# PowerSupply.net
KiCad netlist of a schematic drawn in Altium Designer
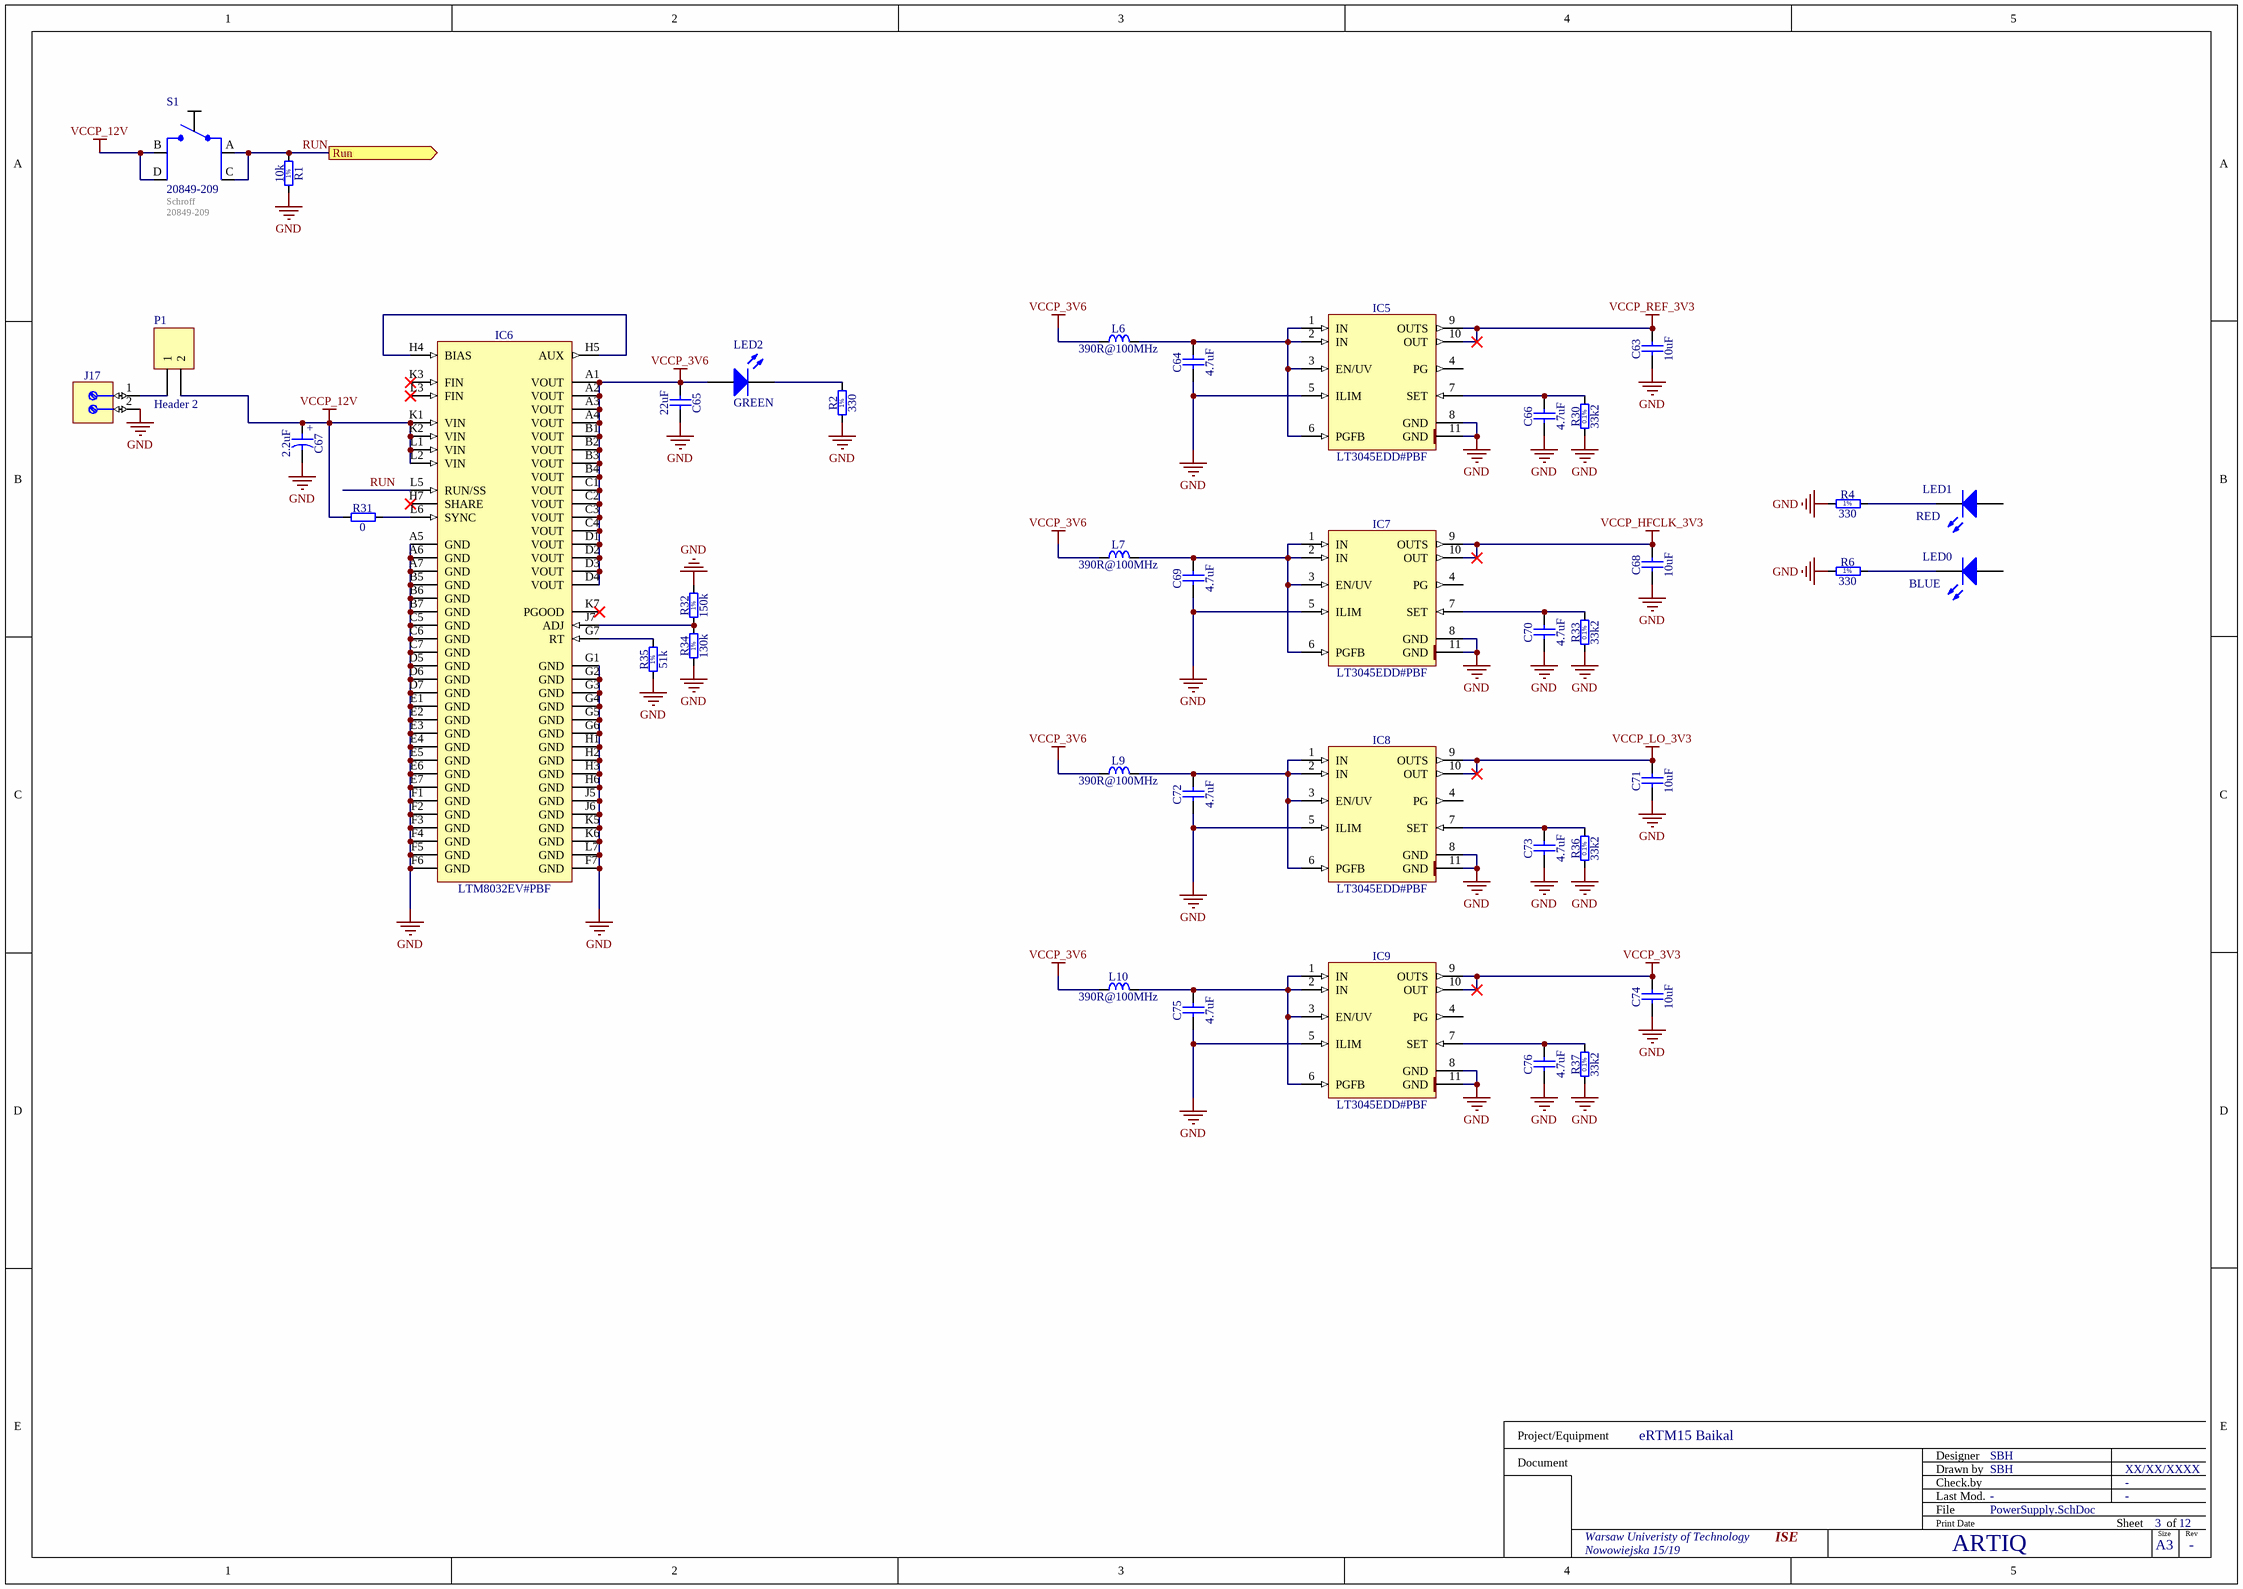
[diagram p0: PowerSupply.SchDoc]

(export (version "E")
  (design (tool "Eeschema 10.0.6"))
  (components
    (comp (ref "C63")
      (value "10uF")
      (footprint "CAPC1608X87N")
      (description "Non-polarised capacitor")
      (fields
        (field (name "PART NUMBER") "CC0603_10UF_6.3V_20%_X5R")
        (field (name "VOLTAGE") "6.3V")
        (field (name "AUTHOR") "CERN DEM JLC")
      )
      (libsource (lib "Capacitors") (part "Capacitor - non polarized"))
    )
    (comp (ref "C64")
      (value "4.7uF")
      (footprint "CAPC1709X95N")
      (description "Non-polarised capacitor")
      (fields
        (field (name "PART NUMBER") "CC0603_4.7UF_16V_10%_X5R")
        (field (name "VOLTAGE") "16V")
        (field (name "AUTHOR") "CERN DEM JLC")
      )
      (libsource (lib "Capacitors") (part "Capacitor - non polarized"))
    )
    (comp (ref "C65")
      (value "22uF")
      (footprint "CAPC3216X180N")
      (description "Non-polarised capacitor")
      (fields
        (field (name "PART NUMBER") "CC1206_22UF_10V_10%_X7R")
        (field (name "VOLTAGE") "10V")
        (field (name "AUTHOR") "CERN DEM JLC")
      )
      (libsource (lib "Capacitors") (part "Capacitor - non polarized"))
    )
    (comp (ref "C66")
      (value "4.7uF")
      (footprint "CAPC1709X95N")
      (description "Non-polarised capacitor")
      (fields
        (field (name "PART NUMBER") "CC0603_4.7UF_16V_10%_X5R")
        (field (name "VOLTAGE") "16V")
        (field (name "AUTHOR") "CERN DEM JLC")
      )
      (libsource (lib "Capacitors") (part "Capacitor - non polarized"))
    )
    (comp (ref "C67")
      (value "2.2uF")
      (footprint "CAPMP3216X180N")
      (description "Polarised capacitor")
      (fields
        (field (name "PART NUMBER") "CTE3216-18_2.2UF_25V_10%")
        (field (name "VOLTAGE") "25V")
        (field (name "AUTHOR") "CERN DEM JLC")
      )
      (libsource (lib "Capacitors") (part "Capacitor - polarized"))
    )
    (comp (ref "C68")
      (value "10uF")
      (footprint "CAPC1608X87N")
      (description "Non-polarised capacitor")
      (fields
        (field (name "PART NUMBER") "CC0603_10UF_6.3V_20%_X5R")
        (field (name "VOLTAGE") "6.3V")
        (field (name "AUTHOR") "CERN DEM JLC")
      )
      (libsource (lib "Capacitors") (part "Capacitor - non polarized"))
    )
    (comp (ref "C69")
      (value "4.7uF")
      (footprint "CAPC1709X95N")
      (description "Non-polarised capacitor")
      (fields
        (field (name "PART NUMBER") "CC0603_4.7UF_16V_10%_X5R")
        (field (name "VOLTAGE") "16V")
        (field (name "AUTHOR") "CERN DEM JLC")
      )
      (libsource (lib "Capacitors") (part "Capacitor - non polarized"))
    )
    (comp (ref "C70")
      (value "4.7uF")
      (footprint "CAPC1709X95N")
      (description "Non-polarised capacitor")
      (fields
        (field (name "PART NUMBER") "CC0603_4.7UF_16V_10%_X5R")
        (field (name "VOLTAGE") "16V")
        (field (name "AUTHOR") "CERN DEM JLC")
      )
      (libsource (lib "Capacitors") (part "Capacitor - non polarized"))
    )
    (comp (ref "C71")
      (value "10uF")
      (footprint "CAPC1608X87N")
      (description "Non-polarised capacitor")
      (fields
        (field (name "PART NUMBER") "CC0603_10UF_6.3V_20%_X5R")
        (field (name "VOLTAGE") "6.3V")
        (field (name "AUTHOR") "CERN DEM JLC")
      )
      (libsource (lib "Capacitors") (part "Capacitor - non polarized"))
    )
    (comp (ref "C72")
      (value "4.7uF")
      (footprint "CAPC1709X95N")
      (description "Non-polarised capacitor")
      (fields
        (field (name "PART NUMBER") "CC0603_4.7UF_16V_10%_X5R")
        (field (name "VOLTAGE") "16V")
        (field (name "AUTHOR") "CERN DEM JLC")
      )
      (libsource (lib "Capacitors") (part "Capacitor - non polarized"))
    )
    (comp (ref "C73")
      (value "4.7uF")
      (footprint "CAPC1709X95N")
      (description "Non-polarised capacitor")
      (fields
        (field (name "PART NUMBER") "CC0603_4.7UF_16V_10%_X5R")
        (field (name "VOLTAGE") "16V")
        (field (name "AUTHOR") "CERN DEM JLC")
      )
      (libsource (lib "Capacitors") (part "Capacitor - non polarized"))
    )
    (comp (ref "C74")
      (value "10uF")
      (footprint "CAPC1608X87N")
      (description "Non-polarised capacitor")
      (fields
        (field (name "PART NUMBER") "CC0603_10UF_6.3V_20%_X5R")
        (field (name "VOLTAGE") "6.3V")
        (field (name "AUTHOR") "CERN DEM JLC")
      )
      (libsource (lib "Capacitors") (part "Capacitor - non polarized"))
    )
    (comp (ref "C75")
      (value "4.7uF")
      (footprint "CAPC1709X95N")
      (description "Non-polarised capacitor")
      (fields
        (field (name "PART NUMBER") "CC0603_4.7UF_16V_10%_X5R")
        (field (name "VOLTAGE") "16V")
        (field (name "AUTHOR") "CERN DEM JLC")
      )
      (libsource (lib "Capacitors") (part "Capacitor - non polarized"))
    )
    (comp (ref "C76")
      (value "4.7uF")
      (footprint "CAPC1709X95N")
      (description "Non-polarised capacitor")
      (fields
        (field (name "PART NUMBER") "CC0603_4.7UF_16V_10%_X5R")
        (field (name "VOLTAGE") "16V")
        (field (name "AUTHOR") "CERN DEM JLC")
      )
      (libsource (lib "Capacitors") (part "Capacitor - non polarized"))
    )
    (comp (ref "IC5")
      (value "LT3045EDD#PBF")
      (footprint "SON50P300X300X80-11N-R175X248")
      (description "20V, 500mA, Ultralow Noise, Ultrahigh PSRR Linear Regulator")
      (fields (field (name "MANUFACTURER") "LINEAR TECHNOLOGY") (field (name "AUTHOR") "CERN DEM JLC"))
      (libsource (lib "ICs And Semiconductors") (part "LT3045EDD"))
    )
    (comp (ref "IC6")
      (value "LTM8032EV#PBF")
      (footprint "LGA71S127P7X11_900X1500X297")
      (description "3V-36V To 0.8V-10V, Iout 2A Ultralow Noise EMC Compliant DC/DC uModule")
      (fields (field (name "MANUFACTURER") "LINEAR TECHNOLOGY") (field (name "AUTHOR") "CERN DEM JLC"))
      (libsource (lib "ICs And Semiconductors") (part "LTM8032"))
    )
    (comp (ref "IC7")
      (value "LT3045EDD#PBF")
      (footprint "SON50P300X300X80-11N-R175X248")
      (description "20V, 500mA, Ultralow Noise, Ultrahigh PSRR Linear Regulator")
      (fields (field (name "MANUFACTURER") "LINEAR TECHNOLOGY") (field (name "AUTHOR") "CERN DEM JLC"))
      (libsource (lib "ICs And Semiconductors") (part "LT3045EDD"))
    )
    (comp (ref "IC8")
      (value "LT3045EDD#PBF")
      (footprint "SON50P300X300X80-11N-R175X248")
      (description "20V, 500mA, Ultralow Noise, Ultrahigh PSRR Linear Regulator")
      (fields (field (name "MANUFACTURER") "LINEAR TECHNOLOGY") (field (name "AUTHOR") "CERN DEM JLC"))
      (libsource (lib "ICs And Semiconductors") (part "LT3045EDD"))
    )
    (comp (ref "IC9")
      (value "LT3045EDD#PBF")
      (footprint "SON50P300X300X80-11N-R175X248")
      (description "20V, 500mA, Ultralow Noise, Ultrahigh PSRR Linear Regulator")
      (fields (field (name "MANUFACTURER") "LINEAR TECHNOLOGY") (field (name "AUTHOR") "CERN DEM JLC"))
      (libsource (lib "ICs And Semiconductors") (part "LT3045EDD"))
    )
    (comp (ref "J17")
      (value "Terminal")
      (footprint "WIELAND_25.161.0253.0")
      (description "Terminal Block, 2 Positions, Screw Connection")
      (fields
        (field (name "PART NUMBER") "WIELAND_25.161.0253.0")
        (field (name "MANUFACTURER") "WIELAND")
        (field (name "AUTHOR") "CERN DEM JLC")
      )
      (libsource (lib "Connectors") (part "Terminal Block_2 Positions_Screw Connection"))
    )
    (comp (ref "L6")
      (value "390R@100MHz")
      (footprint "INDC1608X95N")
      (description "Inductor")
      (fields
        (field (name "PART NUMBER") "IND0603_TDK_MPZ1608R391A")
        (field (name "POWER") "1.2A")
        (field (name "AUTHOR") "CERN DEM JLC")
      )
      (libsource (lib "Inductors & Transformers") (part "Inductor"))
    )
    (comp (ref "L7")
      (value "390R@100MHz")
      (footprint "INDC1608X95N")
      (description "Inductor")
      (fields
        (field (name "PART NUMBER") "IND0603_TDK_MPZ1608R391A")
        (field (name "POWER") "1.2A")
        (field (name "AUTHOR") "CERN DEM JLC")
      )
      (libsource (lib "Inductors & Transformers") (part "Inductor"))
    )
    (comp (ref "L9")
      (value "390R@100MHz")
      (footprint "INDC1608X95N")
      (description "Inductor")
      (fields
        (field (name "PART NUMBER") "IND0603_TDK_MPZ1608R391A")
        (field (name "POWER") "1.2A")
        (field (name "AUTHOR") "CERN DEM JLC")
      )
      (libsource (lib "Inductors & Transformers") (part "Inductor"))
    )
    (comp (ref "L10")
      (value "390R@100MHz")
      (footprint "INDC1608X95N")
      (description "Inductor")
      (fields
        (field (name "PART NUMBER") "IND0603_TDK_MPZ1608R391A")
        (field (name "POWER") "1.2A")
        (field (name "AUTHOR") "CERN DEM JLC")
      )
      (libsource (lib "Inductors & Transformers") (part "Inductor"))
    )
    (comp (ref "LED0")
      (value "BLUE")
      (footprint "0603LED")
      (description "LED")
      (libsource (lib "Miscellaneous Devices") (part "LED2"))
    )
    (comp (ref "LED1")
      (value "RED")
      (footprint "0603LED")
      (description "LED")
      (libsource (lib "Miscellaneous Devices") (part "LED3"))
    )
    (comp (ref "LED2")
      (value "GREEN")
      (footprint "0603LED")
      (description "LED")
      (libsource (lib "Miscellaneous Devices") (part "LED3"))
    )
    (comp (ref "P1")
      (value "Header 2")
      (footprint "HDR1X2")
      (description "Header, 2-Pin")
      (fields (field (name "PUBLISHER") "Altium Limited"))
      (libsource (lib "Miscellaneous Connectors") (part "Header 2"))
    )
    (comp (ref "R1")
      (value "10k")
      (footprint "RESC1005X40N")
      (description "Resistor - 1%")
      (fields
        (field (name "PART NUMBER") "R0402_10K_1%_0.0625W_100PPM")
        (field (name "POWER") "0.0625W")
        (field (name "AUTHOR") "CERN DEM JLC")
      )
      (libsource (lib "Resistors") (part "Resistor - 1%"))
    )
    (comp (ref "R2")
      (value "330")
      (footprint "RESC1005X40N")
      (description "Resistor - 1%")
      (fields
        (field (name "PART NUMBER") "R0402_330R_1%_0.0625W_100PPM")
        (field (name "POWER") "0.0625W")
        (field (name "AUTHOR") "CERN DEM JLC")
      )
      (libsource (lib "Resistors") (part "Resistor - 1%"))
    )
    (comp (ref "R4")
      (value "330")
      (footprint "RESC1005X40N")
      (description "Resistor - 1%")
      (fields
        (field (name "PART NUMBER") "R0402_330R_1%_0.0625W_100PPM")
        (field (name "POWER") "0.0625W")
        (field (name "AUTHOR") "CERN DEM JLC")
      )
      (libsource (lib "Resistors") (part "Resistor - 1%"))
    )
    (comp (ref "R6")
      (value "330")
      (footprint "RESC1005X40N")
      (description "Resistor - 1%")
      (fields
        (field (name "PART NUMBER") "R0402_330R_1%_0.0625W_100PPM")
        (field (name "POWER") "0.0625W")
        (field (name "AUTHOR") "CERN DEM JLC")
      )
      (libsource (lib "Resistors") (part "Resistor - 1%"))
    )
    (comp (ref "R30")
      (value "33k2")
      (footprint "RESC1608X55N")
      (description "Resistor - 0.1%")
      (fields
        (field (name "PART NUMBER") "R0603_33K2_0.1%_0.063W_10PPM")
        (field (name "POWER") "0.063W")
        (field (name "AUTHOR") "CERN DEM JLC")
      )
      (libsource (lib "Resistors") (part "Resistor - 0.1%"))
    )
    (comp (ref "R31")
      (value "0")
      (footprint "RESC1005X40N")
      (description "Resistor")
      (fields
        (field (name "PART NUMBER") "R0402_0R_JUMPER")
        (field (name "MANUFACTURER") "GENERIC")
        (field (name "AUTHOR") "CERN DEM JLC")
      )
      (libsource (lib "Resistors") (part "Resistor"))
    )
    (comp (ref "R32")
      (value "150k")
      (footprint "RESC1005X40N")
      (description "Resistor - 1%")
      (fields
        (field (name "PART NUMBER") "R0402_150K_1%_0.0625W_100PPM")
        (field (name "POWER") "0.0625W")
        (field (name "AUTHOR") "CERN DEM JLC")
      )
      (libsource (lib "Resistors") (part "Resistor - 1%"))
    )
    (comp (ref "R33")
      (value "33k2")
      (footprint "RESC1608X55N")
      (description "Resistor - 0.1%")
      (fields
        (field (name "PART NUMBER") "R0603_33K2_0.1%_0.063W_10PPM")
        (field (name "POWER") "0.063W")
        (field (name "AUTHOR") "CERN DEM JLC")
      )
      (libsource (lib "Resistors") (part "Resistor - 0.1%"))
    )
    (comp (ref "R34")
      (value "130k")
      (footprint "RESC1005X40N")
      (description "Resistor - 1%")
      (fields
        (field (name "PART NUMBER") "R0402_130K_1%_0.0625W_100PPM")
        (field (name "POWER") "0.0625W")
        (field (name "AUTHOR") "CERN DEM JLC")
      )
      (libsource (lib "Resistors") (part "Resistor - 1%"))
    )
    (comp (ref "R35")
      (value "51k")
      (footprint "RESC1005X40N")
      (description "Resistor - 1%")
      (fields
        (field (name "PART NUMBER") "R0402_51K_1%_0.0625W_100PPM")
        (field (name "POWER") "0.0625W")
        (field (name "AUTHOR") "CERN DEM JLC")
      )
      (libsource (lib "Resistors") (part "Resistor - 1%"))
    )
    (comp (ref "R36")
      (value "33k2")
      (footprint "RESC1608X55N")
      (description "Resistor - 0.1%")
      (fields
        (field (name "PART NUMBER") "R0603_33K2_0.1%_0.063W_10PPM")
        (field (name "POWER") "0.063W")
        (field (name "AUTHOR") "CERN DEM JLC")
      )
      (libsource (lib "Resistors") (part "Resistor - 0.1%"))
    )
    (comp (ref "R37")
      (value "33k2")
      (footprint "RESC1608X55N")
      (description "Resistor - 0.1%")
      (fields
        (field (name "PART NUMBER") "R0603_33K2_0.1%_0.063W_10PPM")
        (field (name "POWER") "0.063W")
        (field (name "AUTHOR") "CERN DEM JLC")
      )
      (libsource (lib "Resistors") (part "Resistor - 0.1%"))
    )
    (comp (ref "S1")
      (value "20849-209")
      (footprint "4-pin Switch")
      (description "Mikroschalter fuer AMC-Modul (Schliesser)")
      (fields
        (field (name "MANUFACTURER") "Schroff")
        (field (name "DISTRIBUTOR") "Schroff")
        (field (name "DISTRIBUTORNR") "20849-209")
      )
      (libsource (lib "SchematicComponents") (part "4-pin Switch"))
    )
  )
  (nets
    (net (code "1") (name "/RUN") (class "Default")
      (node (ref "IC6") (pin "L5") (pinfunction "RUN/SS_L5") (pintype "input"))
      (node (ref "R1") (pin "2") (pinfunction "2_2") (pintype "passive"))
      (node (ref "S1") (pin "A") (pinfunction "A_A") (pintype "passive"))
      (node (ref "S1") (pin "C") (pinfunction "C_C") (pintype "passive"))
    )
    (net (code "2") (name "GND") (class "Default")
      (node (ref "C63") (pin "1") (pinfunction "1_1") (pintype "passive"))
      (node (ref "C64") (pin "1") (pinfunction "1_1") (pintype "passive"))
      (node (ref "C65") (pin "2") (pinfunction "2_2") (pintype "passive"))
      (node (ref "C66") (pin "1") (pinfunction "1_1") (pintype "passive"))
      (node (ref "C67") (pin "2") (pinfunction "2_2") (pintype "passive"))
      (node (ref "C68") (pin "1") (pinfunction "1_1") (pintype "passive"))
      (node (ref "C69") (pin "1") (pinfunction "1_1") (pintype "passive"))
      (node (ref "C70") (pin "1") (pinfunction "1_1") (pintype "passive"))
      (node (ref "C71") (pin "1") (pinfunction "1_1") (pintype "passive"))
      (node (ref "C72") (pin "1") (pinfunction "1_1") (pintype "passive"))
      (node (ref "C73") (pin "1") (pinfunction "1_1") (pintype "passive"))
      (node (ref "C74") (pin "1") (pinfunction "1_1") (pintype "passive"))
      (node (ref "C75") (pin "1") (pinfunction "1_1") (pintype "passive"))
      (node (ref "C76") (pin "1") (pinfunction "1_1") (pintype "passive"))
      (node (ref "IC5") (pin "11") (pinfunction "GND_11") (pintype "power_in"))
      (node (ref "IC5") (pin "5") (pinfunction "ILIM_5") (pintype "input"))
      (node (ref "IC5") (pin "8") (pinfunction "GND_8") (pintype "power_in"))
      (node (ref "IC6") (pin "A5") (pinfunction "GND_A5") (pintype "power_in"))
      (node (ref "IC6") (pin "A6") (pinfunction "GND_A6") (pintype "power_in"))
      (node (ref "IC6") (pin "A7") (pinfunction "GND_A7") (pintype "power_in"))
      (node (ref "IC6") (pin "B5") (pinfunction "GND_B5") (pintype "power_in"))
      (node (ref "IC6") (pin "B6") (pinfunction "GND_B6") (pintype "power_in"))
      (node (ref "IC6") (pin "B7") (pinfunction "GND_B7") (pintype "power_in"))
      (node (ref "IC6") (pin "C5") (pinfunction "GND_C5") (pintype "power_in"))
      (node (ref "IC6") (pin "C6") (pinfunction "GND_C6") (pintype "power_in"))
      (node (ref "IC6") (pin "C7") (pinfunction "GND_C7") (pintype "power_in"))
      (node (ref "IC6") (pin "D5") (pinfunction "GND_D5") (pintype "power_in"))
      (node (ref "IC6") (pin "D6") (pinfunction "GND_D6") (pintype "power_in"))
      (node (ref "IC6") (pin "D7") (pinfunction "GND_D7") (pintype "power_in"))
      (node (ref "IC6") (pin "E1") (pinfunction "GND_E1") (pintype "power_in"))
      (node (ref "IC6") (pin "E2") (pinfunction "GND_E2") (pintype "power_in"))
      (node (ref "IC6") (pin "E3") (pinfunction "GND_E3") (pintype "power_in"))
      (node (ref "IC6") (pin "E4") (pinfunction "GND_E4") (pintype "power_in"))
      (node (ref "IC6") (pin "E5") (pinfunction "GND_E5") (pintype "power_in"))
      (node (ref "IC6") (pin "E6") (pinfunction "GND_E6") (pintype "power_in"))
      (node (ref "IC6") (pin "E7") (pinfunction "GND_E7") (pintype "power_in"))
      (node (ref "IC6") (pin "F1") (pinfunction "GND_F1") (pintype "power_in"))
      (node (ref "IC6") (pin "F2") (pinfunction "GND_F2") (pintype "power_in"))
      (node (ref "IC6") (pin "F3") (pinfunction "GND_F3") (pintype "power_in"))
      (node (ref "IC6") (pin "F4") (pinfunction "GND_F4") (pintype "power_in"))
      (node (ref "IC6") (pin "F5") (pinfunction "GND_F5") (pintype "power_in"))
      (node (ref "IC6") (pin "F6") (pinfunction "GND_F6") (pintype "power_in"))
      (node (ref "IC6") (pin "F7") (pinfunction "GND_F7") (pintype "power_in"))
      (node (ref "IC6") (pin "G1") (pinfunction "GND_G1") (pintype "power_in"))
      (node (ref "IC6") (pin "G2") (pinfunction "GND_G2") (pintype "power_in"))
      (node (ref "IC6") (pin "G3") (pinfunction "GND_G3") (pintype "power_in"))
      (node (ref "IC6") (pin "G4") (pinfunction "GND_G4") (pintype "power_in"))
      (node (ref "IC6") (pin "G5") (pinfunction "GND_G5") (pintype "power_in"))
      (node (ref "IC6") (pin "G6") (pinfunction "GND_G6") (pintype "power_in"))
      (node (ref "IC6") (pin "H1") (pinfunction "GND_H1") (pintype "power_in"))
      (node (ref "IC6") (pin "H2") (pinfunction "GND_H2") (pintype "power_in"))
      (node (ref "IC6") (pin "H3") (pinfunction "GND_H3") (pintype "power_in"))
      (node (ref "IC6") (pin "H6") (pinfunction "GND_H6") (pintype "power_in"))
      (node (ref "IC6") (pin "J5") (pinfunction "GND_J5") (pintype "power_in"))
      (node (ref "IC6") (pin "J6") (pinfunction "GND_J6") (pintype "power_in"))
      (node (ref "IC6") (pin "K5") (pinfunction "GND_K5") (pintype "power_in"))
      (node (ref "IC6") (pin "K6") (pinfunction "GND_K6") (pintype "power_in"))
      (node (ref "IC6") (pin "L7") (pinfunction "GND_L7") (pintype "power_in"))
      (node (ref "IC7") (pin "11") (pinfunction "GND_11") (pintype "power_in"))
      (node (ref "IC7") (pin "5") (pinfunction "ILIM_5") (pintype "input"))
      (node (ref "IC7") (pin "8") (pinfunction "GND_8") (pintype "power_in"))
      (node (ref "IC8") (pin "11") (pinfunction "GND_11") (pintype "power_in"))
      (node (ref "IC8") (pin "5") (pinfunction "ILIM_5") (pintype "input"))
      (node (ref "IC8") (pin "8") (pinfunction "GND_8") (pintype "power_in"))
      (node (ref "IC9") (pin "11") (pinfunction "GND_11") (pintype "power_in"))
      (node (ref "IC9") (pin "5") (pinfunction "ILIM_5") (pintype "input"))
      (node (ref "IC9") (pin "8") (pinfunction "GND_8") (pintype "power_in"))
      (node (ref "J17") (pin "2") (pinfunction "2_2") (pintype "bidirectional"))
      (node (ref "R1") (pin "1") (pinfunction "1_1") (pintype "passive"))
      (node (ref "R2") (pin "1") (pinfunction "1_1") (pintype "passive"))
      (node (ref "R30") (pin "1") (pinfunction "1_1") (pintype "passive"))
      (node (ref "R32") (pin "2") (pinfunction "2_2") (pintype "passive"))
      (node (ref "R33") (pin "1") (pinfunction "1_1") (pintype "passive"))
      (node (ref "R34") (pin "1") (pinfunction "1_1") (pintype "passive"))
      (node (ref "R35") (pin "1") (pinfunction "1_1") (pintype "passive"))
      (node (ref "R36") (pin "1") (pinfunction "1_1") (pintype "passive"))
      (node (ref "R37") (pin "1") (pinfunction "1_1") (pintype "passive"))
      (node (ref "R4") (pin "1") (pinfunction "1_1") (pintype "passive"))
      (node (ref "R6") (pin "1") (pinfunction "1_1") (pintype "passive"))
    )
    (net (code "3") (name "Net-(IC5-EN{slash}UV)") (class "Default")
      (node (ref "C64") (pin "2") (pinfunction "2_2") (pintype "passive"))
      (node (ref "IC5") (pin "1") (pinfunction "IN_1") (pintype "input"))
      (node (ref "IC5") (pin "2") (pinfunction "IN_2") (pintype "input"))
      (node (ref "IC5") (pin "3") (pinfunction "EN/UV_3") (pintype "input"))
      (node (ref "IC5") (pin "6") (pinfunction "PGFB_6") (pintype "input"))
      (node (ref "L6") (pin "2") (pinfunction "2_2") (pintype "passive"))
    )
    (net (code "4") (name "Net-(IC5-SET)") (class "Default")
      (node (ref "C66") (pin "2") (pinfunction "2_2") (pintype "passive"))
      (node (ref "IC5") (pin "7") (pinfunction "SET_7") (pintype "input"))
      (node (ref "R30") (pin "2") (pinfunction "2_2") (pintype "passive"))
    )
    (net (code "5") (name "Net-(IC6-ADJ)") (class "Default")
      (node (ref "IC6") (pin "J7") (pinfunction "ADJ_J7") (pintype "input"))
      (node (ref "R32") (pin "1") (pinfunction "1_1") (pintype "passive"))
      (node (ref "R34") (pin "2") (pinfunction "2_2") (pintype "passive"))
    )
    (net (code "6") (name "Net-(IC6-AUX)") (class "Default")
      (node (ref "IC6") (pin "H4") (pinfunction "BIAS_H4") (pintype "input"))
      (node (ref "IC6") (pin "H5") (pinfunction "AUX_H5") (pintype "output"))
    )
    (net (code "7") (name "Net-(IC6-RT)") (class "Default")
      (node (ref "IC6") (pin "G7") (pinfunction "RT_G7") (pintype "input"))
      (node (ref "R35") (pin "2") (pinfunction "2_2") (pintype "passive"))
    )
    (net (code "8") (name "Net-(IC6-SYNC)") (class "Default")
      (node (ref "IC6") (pin "L6") (pinfunction "SYNC_L6") (pintype "input"))
      (node (ref "R31") (pin "2") (pinfunction "2_2") (pintype "passive"))
    )
    (net (code "9") (name "Net-(IC7-EN{slash}UV)") (class "Default")
      (node (ref "C69") (pin "2") (pinfunction "2_2") (pintype "passive"))
      (node (ref "IC7") (pin "1") (pinfunction "IN_1") (pintype "input"))
      (node (ref "IC7") (pin "2") (pinfunction "IN_2") (pintype "input"))
      (node (ref "IC7") (pin "3") (pinfunction "EN/UV_3") (pintype "input"))
      (node (ref "IC7") (pin "6") (pinfunction "PGFB_6") (pintype "input"))
      (node (ref "L7") (pin "2") (pinfunction "2_2") (pintype "passive"))
    )
    (net (code "10") (name "Net-(IC7-SET)") (class "Default")
      (node (ref "C70") (pin "2") (pinfunction "2_2") (pintype "passive"))
      (node (ref "IC7") (pin "7") (pinfunction "SET_7") (pintype "input"))
      (node (ref "R33") (pin "2") (pinfunction "2_2") (pintype "passive"))
    )
    (net (code "11") (name "Net-(IC8-EN{slash}UV)") (class "Default")
      (node (ref "C72") (pin "2") (pinfunction "2_2") (pintype "passive"))
      (node (ref "IC8") (pin "1") (pinfunction "IN_1") (pintype "input"))
      (node (ref "IC8") (pin "2") (pinfunction "IN_2") (pintype "input"))
      (node (ref "IC8") (pin "3") (pinfunction "EN/UV_3") (pintype "input"))
      (node (ref "IC8") (pin "6") (pinfunction "PGFB_6") (pintype "input"))
      (node (ref "L9") (pin "2") (pinfunction "2_2") (pintype "passive"))
    )
    (net (code "12") (name "Net-(IC8-SET)") (class "Default")
      (node (ref "C73") (pin "2") (pinfunction "2_2") (pintype "passive"))
      (node (ref "IC8") (pin "7") (pinfunction "SET_7") (pintype "input"))
      (node (ref "R36") (pin "2") (pinfunction "2_2") (pintype "passive"))
    )
    (net (code "13") (name "Net-(IC9-EN{slash}UV)") (class "Default")
      (node (ref "C75") (pin "2") (pinfunction "2_2") (pintype "passive"))
      (node (ref "IC9") (pin "1") (pinfunction "IN_1") (pintype "input"))
      (node (ref "IC9") (pin "2") (pinfunction "IN_2") (pintype "input"))
      (node (ref "IC9") (pin "3") (pinfunction "EN/UV_3") (pintype "input"))
      (node (ref "IC9") (pin "6") (pinfunction "PGFB_6") (pintype "input"))
      (node (ref "L10") (pin "2") (pinfunction "2_2") (pintype "passive"))
    )
    (net (code "14") (name "Net-(IC9-SET)") (class "Default")
      (node (ref "C76") (pin "2") (pinfunction "2_2") (pintype "passive"))
      (node (ref "IC9") (pin "7") (pinfunction "SET_7") (pintype "input"))
      (node (ref "R37") (pin "2") (pinfunction "2_2") (pintype "passive"))
    )
    (net (code "15") (name "Net-(J17-Pad1)") (class "Default")
      (node (ref "J17") (pin "1") (pinfunction "1_1") (pintype "bidirectional"))
      (node (ref "P1") (pin "1") (pinfunction "1_1") (pintype "passive"))
    )
    (net (code "16") (name "Net-(LED0-K)") (class "Default")
      (node (ref "LED0") (pin "2") (pinfunction "K_2") (pintype "passive"))
      (node (ref "R6") (pin "2") (pinfunction "2_2") (pintype "passive"))
    )
    (net (code "17") (name "Net-(LED1-K)") (class "Default")
      (node (ref "LED1") (pin "2") (pinfunction "K_2") (pintype "passive"))
      (node (ref "R4") (pin "2") (pinfunction "2_2") (pintype "passive"))
    )
    (net (code "18") (name "Net-(LED2-K)") (class "Default")
      (node (ref "LED2") (pin "2") (pinfunction "K_2") (pintype "passive"))
      (node (ref "R2") (pin "2") (pinfunction "2_2") (pintype "passive"))
    )
    (net (code "19") (name "VCCP_3V3") (class "Default")
      (node (ref "C74") (pin "2") (pinfunction "2_2") (pintype "passive"))
      (node (ref "IC9") (pin "10") (pinfunction "OUT_10") (pintype "output"))
      (node (ref "IC9") (pin "9") (pinfunction "OUTS_9") (pintype "output"))
    )
    (net (code "20") (name "VCCP_3V6") (class "Default")
      (node (ref "C65") (pin "1") (pinfunction "1_1") (pintype "passive"))
      (node (ref "IC6") (pin "A1") (pinfunction "VOUT_A1") (pintype "power_in"))
      (node (ref "IC6") (pin "A2") (pinfunction "VOUT_A2") (pintype "power_in"))
      (node (ref "IC6") (pin "A3") (pinfunction "VOUT_A3") (pintype "power_in"))
      (node (ref "IC6") (pin "A4") (pinfunction "VOUT_A4") (pintype "power_in"))
      (node (ref "IC6") (pin "B1") (pinfunction "VOUT_B1") (pintype "power_in"))
      (node (ref "IC6") (pin "B2") (pinfunction "VOUT_B2") (pintype "power_in"))
      (node (ref "IC6") (pin "B3") (pinfunction "VOUT_B3") (pintype "power_in"))
      (node (ref "IC6") (pin "B4") (pinfunction "VOUT_B4") (pintype "power_in"))
      (node (ref "IC6") (pin "C1") (pinfunction "VOUT_C1") (pintype "power_in"))
      (node (ref "IC6") (pin "C2") (pinfunction "VOUT_C2") (pintype "power_in"))
      (node (ref "IC6") (pin "C3") (pinfunction "VOUT_C3") (pintype "power_in"))
      (node (ref "IC6") (pin "C4") (pinfunction "VOUT_C4") (pintype "power_in"))
      (node (ref "IC6") (pin "D1") (pinfunction "VOUT_D1") (pintype "power_in"))
      (node (ref "IC6") (pin "D2") (pinfunction "VOUT_D2") (pintype "power_in"))
      (node (ref "IC6") (pin "D3") (pinfunction "VOUT_D3") (pintype "power_in"))
      (node (ref "IC6") (pin "D4") (pinfunction "VOUT_D4") (pintype "power_in"))
      (node (ref "L10") (pin "1") (pinfunction "1_1") (pintype "passive"))
      (node (ref "L6") (pin "1") (pinfunction "1_1") (pintype "passive"))
      (node (ref "L7") (pin "1") (pinfunction "1_1") (pintype "passive"))
      (node (ref "L9") (pin "1") (pinfunction "1_1") (pintype "passive"))
      (node (ref "LED2") (pin "1") (pinfunction "A_1") (pintype "passive"))
    )
    (net (code "21") (name "VCCP_12V") (class "Default")
      (node (ref "C67") (pin "1") (pinfunction "1_1") (pintype "passive"))
      (node (ref "IC6") (pin "K1") (pinfunction "VIN_K1") (pintype "input"))
      (node (ref "IC6") (pin "K2") (pinfunction "VIN_K2") (pintype "input"))
      (node (ref "IC6") (pin "L1") (pinfunction "VIN_L1") (pintype "input"))
      (node (ref "IC6") (pin "L2") (pinfunction "VIN_L2") (pintype "input"))
      (node (ref "P1") (pin "2") (pinfunction "2_2") (pintype "passive"))
      (node (ref "R31") (pin "1") (pinfunction "1_1") (pintype "passive"))
      (node (ref "S1") (pin "B") (pinfunction "B_B") (pintype "passive"))
      (node (ref "S1") (pin "D") (pinfunction "D_D") (pintype "passive"))
    )
    (net (code "22") (name "VCCP_HFCLK_3V3") (class "Default")
      (node (ref "C68") (pin "2") (pinfunction "2_2") (pintype "passive"))
      (node (ref "IC7") (pin "10") (pinfunction "OUT_10") (pintype "output"))
      (node (ref "IC7") (pin "9") (pinfunction "OUTS_9") (pintype "output"))
    )
    (net (code "23") (name "VCCP_LO_3V3") (class "Default")
      (node (ref "C71") (pin "2") (pinfunction "2_2") (pintype "passive"))
      (node (ref "IC8") (pin "10") (pinfunction "OUT_10") (pintype "output"))
      (node (ref "IC8") (pin "9") (pinfunction "OUTS_9") (pintype "output"))
    )
    (net (code "24") (name "VCCP_REF_3V3") (class "Default")
      (node (ref "C63") (pin "2") (pinfunction "2_2") (pintype "passive"))
      (node (ref "IC5") (pin "10") (pinfunction "OUT_10") (pintype "output"))
      (node (ref "IC5") (pin "9") (pinfunction "OUTS_9") (pintype "output"))
    )
    (net (code "25") (name "unconnected-(IC5-PG-Pad4)") (class "Default")
      (node (ref "IC5") (pin "4") (pinfunction "PG_4") (pintype "output"))
    )
    (net (code "26") (name "unconnected-(IC6-FIN-PadK3)") (class "Default")
      (node (ref "IC6") (pin "K3") (pinfunction "FIN_K3") (pintype "input+no_connect"))
    )
    (net (code "27") (name "unconnected-(IC6-FIN-PadL3)") (class "Default")
      (node (ref "IC6") (pin "L3") (pinfunction "FIN_L3") (pintype "input+no_connect"))
    )
    (net (code "28") (name "unconnected-(IC6-PGOOD-PadK7)") (class "Default")
      (node (ref "IC6") (pin "K7") (pinfunction "PGOOD_K7") (pintype "open_collector+no_connect"))
    )
    (net (code "29") (name "unconnected-(IC6-SHARE-PadH7)") (class "Default")
      (node (ref "IC6") (pin "H7") (pinfunction "SHARE_H7") (pintype "passive+no_connect"))
    )
    (net (code "30") (name "unconnected-(IC7-PG-Pad4)") (class "Default")
      (node (ref "IC7") (pin "4") (pinfunction "PG_4") (pintype "output"))
    )
    (net (code "31") (name "unconnected-(IC8-PG-Pad4)") (class "Default")
      (node (ref "IC8") (pin "4") (pinfunction "PG_4") (pintype "output"))
    )
    (net (code "32") (name "unconnected-(IC9-PG-Pad4)") (class "Default")
      (node (ref "IC9") (pin "4") (pinfunction "PG_4") (pintype "output"))
    )
    (net (code "33") (name "unconnected-(LED0-A-Pad1)") (class "Default")
      (node (ref "LED0") (pin "1") (pinfunction "A_1") (pintype "passive"))
    )
    (net (code "34") (name "unconnected-(LED1-A-Pad1)") (class "Default")
      (node (ref "LED1") (pin "1") (pinfunction "A_1") (pintype "passive"))
    )
  )
)
